# espurna-h.net
KiCad netlist of a schematic drawn in EAGLE
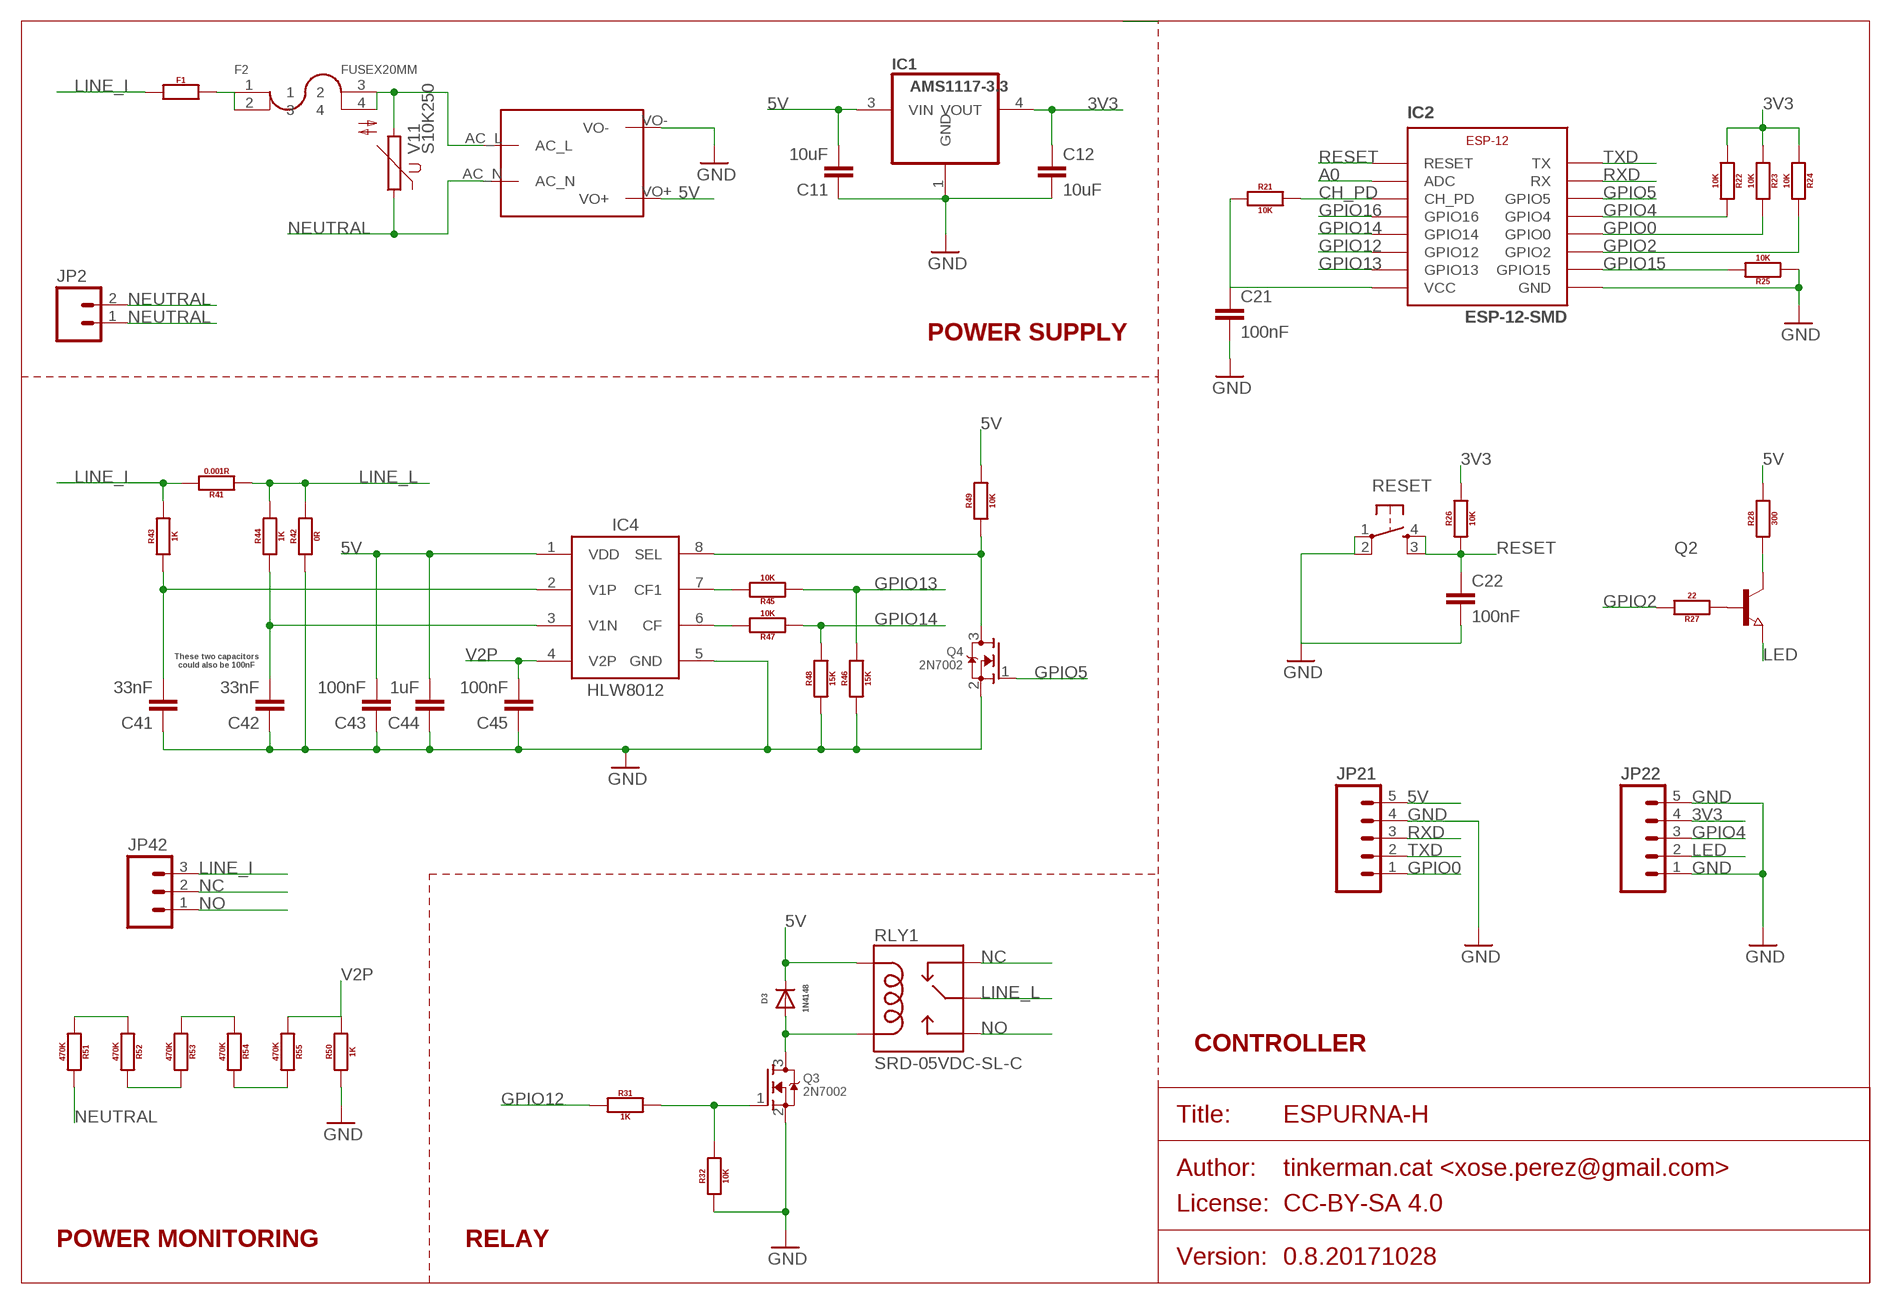
[diagram p0: schematic, sheet 1]

(export (version "E")
  (design (tool "Eeschema 10.0.6"))
  (components
    (comp (ref "C11")
      (value "10uF")
      (footprint "eagle-import:0805")
      (libsource (lib "eagle-import") (part "C-EU0805"))
    )
    (comp (ref "C12")
      (value "10uF")
      (footprint "eagle-import:0805")
      (libsource (lib "eagle-import") (part "C-EU0805"))
    )
    (comp (ref "C21")
      (value "100nF")
      (footprint "eagle-import:0805")
      (libsource (lib "eagle-import") (part "C-EU0805"))
    )
    (comp (ref "C22")
      (value "100nF")
      (footprint "eagle-import:0805")
      (libsource (lib "eagle-import") (part "C-EU0805"))
    )
    (comp (ref "C41")
      (value "33nF")
      (footprint "eagle-import:0805")
      (libsource (lib "eagle-import") (part "C-EU0805"))
    )
    (comp (ref "C42")
      (value "33nF")
      (footprint "eagle-import:0805")
      (libsource (lib "eagle-import") (part "C-EU0805"))
    )
    (comp (ref "C43")
      (value "100nF")
      (footprint "eagle-import:0805")
      (libsource (lib "eagle-import") (part "C-EU0805"))
    )
    (comp (ref "C44")
      (value "1uF")
      (footprint "eagle-import:0805")
      (libsource (lib "eagle-import") (part "C-EU0805"))
    )
    (comp (ref "C45")
      (value "100nF")
      (footprint "eagle-import:0805")
      (libsource (lib "eagle-import") (part "C-EU0805"))
    )
    (comp (ref "D3")
      (value "1N4148")
      (footprint "eagle-import:SOD80")
      (libsource (lib "eagle-import") (part "DIODE"))
    )
    (comp (ref "F1")
      (value "THERMALFUSE0.4")
      (footprint "eagle-import:AXIAL-0.4")
      (libsource (lib "eagle-import") (part "THERMALFUSE0.4"))
    )
    (comp (ref "F2")
      (value "FUSEX20MM")
      (footprint "eagle-import:FUSE_5MM")
      (libsource (lib "eagle-import") (part "FUSEX20MM"))
    )
    (comp (ref "IC1")
      (value "AMS1117-3.3")
      (footprint "eagle-import:SOT223")
      (libsource (lib "eagle-import") (part "REG1117SOT223-2"))
    )
    (comp (ref "IC2")
      (value "ESP-12-SMD")
      (footprint "eagle-import:ESP-12-SMD")
      (libsource (lib "eagle-import") (part "ESP-12-SMD"))
    )
    (comp (ref "IC4")
      (value "HLW8012")
      (footprint "eagle-import:SOP8")
      (libsource (lib "eagle-import") (part "HLW8012"))
    )
    (comp (ref "JP2")
      (value "M02200MIL")
      (footprint "eagle-import:SCREWTERMINAL-200MIL-2")
      (libsource (lib "eagle-import") (part "M02200MIL"))
    )
    (comp (ref "JP21")
      (value "M05PTH")
      (footprint "eagle-import:1X05")
      (libsource (lib "eagle-import") (part "M05PTH"))
    )
    (comp (ref "JP22")
      (value "M05PTH")
      (footprint "eagle-import:1X05")
      (libsource (lib "eagle-import") (part "M05PTH"))
    )
    (comp (ref "JP42")
      (value "M03200MIL")
      (footprint "eagle-import:SCREWTERMINAL-200MIL-3")
      (libsource (lib "eagle-import") (part "M03200MIL"))
    )
    (comp (ref "Q2")
      (value "NPN-TRANSISTOR_SOT23")
      (footprint "eagle-import:SOT23")
      (libsource (lib "eagle-import") (part "NPN-TRANSISTOR_SOT23"))
    )
    (comp (ref "Q3")
      (value "2N7002")
      (footprint "eagle-import:SOT23")
      (libsource (lib "eagle-import") (part "MOSFET-NREFLOW"))
    )
    (comp (ref "Q4")
      (value "2N7002")
      (footprint "eagle-import:SOT23")
      (libsource (lib "eagle-import") (part "MOSFET-NREFLOW"))
    )
    (comp (ref "R21")
      (value "10K")
      (footprint "eagle-import:0805")
      (libsource (lib "eagle-import") (part "RESISTOR0805"))
    )
    (comp (ref "R22")
      (value "10K")
      (footprint "eagle-import:0805")
      (libsource (lib "eagle-import") (part "RESISTOR0805"))
    )
    (comp (ref "R23")
      (value "10K")
      (footprint "eagle-import:0805")
      (libsource (lib "eagle-import") (part "RESISTOR0805"))
    )
    (comp (ref "R24")
      (value "10K")
      (footprint "eagle-import:0805")
      (libsource (lib "eagle-import") (part "RESISTOR0805"))
    )
    (comp (ref "R25")
      (value "10K")
      (footprint "eagle-import:0805")
      (libsource (lib "eagle-import") (part "RESISTOR0805"))
    )
    (comp (ref "R26")
      (value "10K")
      (footprint "eagle-import:0805")
      (libsource (lib "eagle-import") (part "RESISTOR0805"))
    )
    (comp (ref "R27")
      (value "22")
      (footprint "eagle-import:0805")
      (libsource (lib "eagle-import") (part "RESISTOR0805"))
    )
    (comp (ref "R28")
      (value "300")
      (footprint "eagle-import:0805")
      (libsource (lib "eagle-import") (part "RESISTOR0805"))
    )
    (comp (ref "R31")
      (value "1K")
      (footprint "eagle-import:0805")
      (libsource (lib "eagle-import") (part "RESISTOR0805"))
    )
    (comp (ref "R32")
      (value "10K")
      (footprint "eagle-import:0805")
      (libsource (lib "eagle-import") (part "RESISTOR0805"))
    )
    (comp (ref "R41")
      (value "0.001R")
      (footprint "eagle-import:2512")
      (libsource (lib "eagle-import") (part "RESISTOR2512"))
    )
    (comp (ref "R42")
      (value "0R")
      (footprint "eagle-import:1206")
      (libsource (lib "eagle-import") (part "RESISTOR1206"))
    )
    (comp (ref "R43")
      (value "1K")
      (footprint "eagle-import:0805")
      (libsource (lib "eagle-import") (part "RESISTOR0805"))
    )
    (comp (ref "R44")
      (value "1K")
      (footprint "eagle-import:0805")
      (libsource (lib "eagle-import") (part "RESISTOR0805"))
    )
    (comp (ref "R45")
      (value "10K")
      (footprint "eagle-import:0805")
      (libsource (lib "eagle-import") (part "RESISTOR0805"))
    )
    (comp (ref "R46")
      (value "15K")
      (footprint "eagle-import:0805")
      (libsource (lib "eagle-import") (part "RESISTOR0805"))
    )
    (comp (ref "R47")
      (value "10K")
      (footprint "eagle-import:0805")
      (libsource (lib "eagle-import") (part "RESISTOR0805"))
    )
    (comp (ref "R48")
      (value "15K")
      (footprint "eagle-import:0805")
      (libsource (lib "eagle-import") (part "RESISTOR0805"))
    )
    (comp (ref "R49")
      (value "10K")
      (footprint "eagle-import:0805")
      (libsource (lib "eagle-import") (part "RESISTOR0805"))
    )
    (comp (ref "R50")
      (value "1K")
      (footprint "eagle-import:0805")
      (libsource (lib "eagle-import") (part "RESISTOR0805"))
    )
    (comp (ref "R51")
      (value "470K")
      (footprint "eagle-import:0805")
      (libsource (lib "eagle-import") (part "RESISTOR0805"))
    )
    (comp (ref "R52")
      (value "470K")
      (footprint "eagle-import:0805")
      (libsource (lib "eagle-import") (part "RESISTOR0805"))
    )
    (comp (ref "R53")
      (value "470K")
      (footprint "eagle-import:0805")
      (libsource (lib "eagle-import") (part "RESISTOR0805"))
    )
    (comp (ref "R54")
      (value "470K")
      (footprint "eagle-import:0805")
      (libsource (lib "eagle-import") (part "RESISTOR0805"))
    )
    (comp (ref "R55")
      (value "470K")
      (footprint "eagle-import:0805")
      (libsource (lib "eagle-import") (part "RESISTOR0805"))
    )
    (comp (ref "RESET")
      (value "TACTILE_BUTTON_SMD")
      (footprint "eagle-import:TACTILE-BUTTON-SMD")
      (libsource (lib "eagle-import") (part "TACTILE_BUTTON_SMD"))
    )
    (comp (ref "RLY1")
      (value "SRD-05VDC-SL-C")
      (footprint "eagle-import:SRD-5VDC-SL-C")
      (libsource (lib "eagle-import") (part "RELAYSONGLE"))
    )
    (comp (ref "U$1")
      (value "MAINS_CONVERTERS")
      (footprint "eagle-import:HLK-PM01")
      (libsource (lib "eagle-import") (part "MAINS_CONVERTERS"))
    )
    (comp (ref "V11")
      (value "S10K250")
      (footprint "eagle-import:S10K250")
      (libsource (lib "eagle-import") (part "S10K250"))
    )
  )
  (nets
    (net (code "1") (name "/3V3") (class "Default")
      (node (ref "C12") (pin "1") (pinfunction "1_1") (pintype "passive"))
      (node (ref "C21") (pin "1") (pinfunction "1_1") (pintype "passive"))
      (node (ref "IC1") (pin "4") (pinfunction "VOUT_4") (pintype "output"))
      (node (ref "IC2") (pin "VCC") (pinfunction "VCC_VCC") (pintype "bidirectional"))
      (node (ref "JP22") (pin "4") (pinfunction "4_4") (pintype "passive"))
      (node (ref "R21") (pin "1") (pinfunction "1_1") (pintype "passive"))
      (node (ref "R22") (pin "1") (pinfunction "1_1") (pintype "passive"))
      (node (ref "R23") (pin "1") (pinfunction "1_1") (pintype "passive"))
      (node (ref "R24") (pin "1") (pinfunction "1_1") (pintype "passive"))
      (node (ref "R26") (pin "2") (pinfunction "2_2") (pintype "passive"))
    )
    (net (code "2") (name "/5V") (class "Default")
      (node (ref "C11") (pin "2") (pinfunction "2_2") (pintype "passive"))
      (node (ref "C43") (pin "2") (pinfunction "2_2") (pintype "passive"))
      (node (ref "C44") (pin "2") (pinfunction "2_2") (pintype "passive"))
      (node (ref "D3") (pin "2") (pinfunction "C_2") (pintype "passive"))
      (node (ref "IC1") (pin "3") (pinfunction "VIN_3") (pintype "input"))
      (node (ref "IC4") (pin "1") (pinfunction "VDD_1") (pintype "power_in"))
      (node (ref "JP21") (pin "5") (pinfunction "5_5") (pintype "passive"))
      (node (ref "R28") (pin "2") (pinfunction "2_2") (pintype "passive"))
      (node (ref "R49") (pin "2") (pinfunction "2_2") (pintype "passive"))
      (node (ref "RLY1") (pin "COIL1") (pinfunction "COIL1_COIL1") (pintype "bidirectional"))
      (node (ref "U$1") (pin "VO+") (pinfunction "VO+_VO+") (pintype "output"))
    )
    (net (code "3") (name "/A0") (class "Default")
      (node (ref "IC2") (pin "ADC") (pinfunction "ADC_ADC") (pintype "bidirectional"))
    )
    (net (code "4") (name "/CH_PD") (class "Default")
      (node (ref "IC2") (pin "CH_PD") (pinfunction "CH_PD_CH_PD") (pintype "bidirectional"))
      (node (ref "R21") (pin "2") (pinfunction "2_2") (pintype "passive"))
    )
    (net (code "5") (name "/GPIO0") (class "Default")
      (node (ref "IC2") (pin "GPIO0") (pinfunction "GPIO0_GPIO0") (pintype "bidirectional"))
      (node (ref "JP21") (pin "1") (pinfunction "1_1") (pintype "passive"))
      (node (ref "R23") (pin "2") (pinfunction "2_2") (pintype "passive"))
    )
    (net (code "6") (name "/GPIO2") (class "Default")
      (node (ref "IC2") (pin "GPIO2") (pinfunction "GPIO2_GPIO2") (pintype "bidirectional"))
      (node (ref "R24") (pin "2") (pinfunction "2_2") (pintype "passive"))
      (node (ref "R27") (pin "2") (pinfunction "2_2") (pintype "passive"))
    )
    (net (code "7") (name "/GPIO4") (class "Default")
      (node (ref "IC2") (pin "GPIO4") (pinfunction "GPIO4_GPIO4") (pintype "bidirectional"))
      (node (ref "JP22") (pin "3") (pinfunction "3_3") (pintype "passive"))
      (node (ref "R22") (pin "2") (pinfunction "2_2") (pintype "passive"))
    )
    (net (code "8") (name "/GPIO5") (class "Default")
      (node (ref "IC2") (pin "GPIO5") (pinfunction "GPIO5_GPIO5") (pintype "bidirectional"))
      (node (ref "Q4") (pin "1") (pinfunction "G_1") (pintype "bidirectional"))
    )
    (net (code "9") (name "/GPIO12") (class "Default")
      (node (ref "IC2") (pin "GPIO12") (pinfunction "GPIO12_GPIO12") (pintype "bidirectional"))
      (node (ref "R31") (pin "1") (pinfunction "1_1") (pintype "passive"))
    )
    (net (code "10") (name "/GPIO13") (class "Default")
      (node (ref "IC2") (pin "GPIO13") (pinfunction "GPIO13_GPIO13") (pintype "bidirectional"))
      (node (ref "R45") (pin "1") (pinfunction "1_1") (pintype "passive"))
      (node (ref "R46") (pin "2") (pinfunction "2_2") (pintype "passive"))
    )
    (net (code "11") (name "/GPIO14") (class "Default")
      (node (ref "IC2") (pin "GPIO14") (pinfunction "GPIO14_GPIO14") (pintype "bidirectional"))
      (node (ref "R47") (pin "1") (pinfunction "1_1") (pintype "passive"))
      (node (ref "R48") (pin "2") (pinfunction "2_2") (pintype "passive"))
    )
    (net (code "12") (name "/GPIO15") (class "Default")
      (node (ref "IC2") (pin "GPIO15") (pinfunction "GPIO15_GPIO15") (pintype "bidirectional"))
      (node (ref "R25") (pin "2") (pinfunction "2_2") (pintype "passive"))
    )
    (net (code "13") (name "/GPIO16") (class "Default")
      (node (ref "IC2") (pin "GPIO16") (pinfunction "GPIO16_GPIO16") (pintype "bidirectional"))
    )
    (net (code "14") (name "/LED") (class "Default")
      (node (ref "JP22") (pin "2") (pinfunction "2_2") (pintype "passive"))
      (node (ref "Q2") (pin "2") (pinfunction "E_2") (pintype "passive"))
    )
    (net (code "15") (name "/LINE_I") (class "Default")
      (node (ref "F1") (pin "P$1") (pinfunction "1_P$1") (pintype "passive"))
      (node (ref "JP42") (pin "3") (pinfunction "3_3") (pintype "passive"))
      (node (ref "R41") (pin "2") (pinfunction "2_2") (pintype "passive"))
      (node (ref "R43") (pin "2") (pinfunction "2_2") (pintype "passive"))
    )
    (net (code "16") (name "/LINE_L") (class "Default")
      (node (ref "R41") (pin "1") (pinfunction "1_1") (pintype "passive"))
      (node (ref "R42") (pin "2") (pinfunction "2_2") (pintype "passive"))
      (node (ref "R44") (pin "2") (pinfunction "2_2") (pintype "passive"))
      (node (ref "RLY1") (pin "COMMON") (pinfunction "MAIN_COMMON") (pintype "bidirectional"))
    )
    (net (code "17") (name "/NC") (class "Default")
      (node (ref "JP42") (pin "2") (pinfunction "2_2") (pintype "passive"))
      (node (ref "RLY1") (pin "CLOSED") (pinfunction "NC_CLOSED") (pintype "bidirectional"))
    )
    (net (code "18") (name "/NEUTRAL") (class "Default")
      (node (ref "JP2") (pin "1") (pinfunction "1_1") (pintype "passive"))
      (node (ref "JP2") (pin "2") (pinfunction "2_2") (pintype "passive"))
      (node (ref "R51") (pin "2") (pinfunction "2_2") (pintype "passive"))
      (node (ref "U$1") (pin "AC_N") (pinfunction "AC_N_AC_N") (pintype "input"))
      (node (ref "V11") (pin "1") (pinfunction "1_1") (pintype "passive"))
    )
    (net (code "19") (name "/NO") (class "Default")
      (node (ref "JP42") (pin "1") (pinfunction "1_1") (pintype "passive"))
      (node (ref "RLY1") (pin "OPEN") (pinfunction "NO_OPEN") (pintype "bidirectional"))
    )
    (net (code "20") (name "/RESET") (class "Default")
      (node (ref "C22") (pin "1") (pinfunction "1_1") (pintype "passive"))
      (node (ref "IC2") (pin "RESET") (pinfunction "RESET_RESET") (pintype "bidirectional"))
      (node (ref "R26") (pin "1") (pinfunction "1_1") (pintype "passive"))
      (node (ref "RESET") (pin "3") (pinfunction "SWB2_3") (pintype "passive"))
      (node (ref "RESET") (pin "4") (pinfunction "SWA2_4") (pintype "passive"))
    )
    (net (code "21") (name "/RXD") (class "Default")
      (node (ref "IC2") (pin "RX") (pinfunction "RX_RX") (pintype "bidirectional"))
      (node (ref "JP21") (pin "3") (pinfunction "3_3") (pintype "passive"))
    )
    (net (code "22") (name "/TXD") (class "Default")
      (node (ref "IC2") (pin "TX") (pinfunction "TX_TX") (pintype "bidirectional"))
      (node (ref "JP21") (pin "2") (pinfunction "2_2") (pintype "passive"))
    )
    (net (code "23") (name "/V2P") (class "Default")
      (node (ref "C45") (pin "2") (pinfunction "2_2") (pintype "passive"))
      (node (ref "IC4") (pin "4") (pinfunction "V2P_4") (pintype "input"))
      (node (ref "R50") (pin "2") (pinfunction "2_2") (pintype "passive"))
      (node (ref "R55") (pin "1") (pinfunction "1_1") (pintype "passive"))
    )
    (net (code "24") (name "GND") (class "Default")
      (node (ref "C11") (pin "1") (pinfunction "1_1") (pintype "passive"))
      (node (ref "C12") (pin "2") (pinfunction "2_2") (pintype "passive"))
      (node (ref "C21") (pin "2") (pinfunction "2_2") (pintype "passive"))
      (node (ref "C22") (pin "2") (pinfunction "2_2") (pintype "passive"))
      (node (ref "C41") (pin "1") (pinfunction "1_1") (pintype "passive"))
      (node (ref "C42") (pin "1") (pinfunction "1_1") (pintype "passive"))
      (node (ref "C43") (pin "1") (pinfunction "1_1") (pintype "passive"))
      (node (ref "C44") (pin "1") (pinfunction "1_1") (pintype "passive"))
      (node (ref "C45") (pin "1") (pinfunction "1_1") (pintype "passive"))
      (node (ref "IC1") (pin "1") (pinfunction "GND_1") (pintype "power_in"))
      (node (ref "IC2") (pin "GND") (pinfunction "GND_GND") (pintype "bidirectional"))
      (node (ref "IC4") (pin "5") (pinfunction "GND_5") (pintype "power_in"))
      (node (ref "JP21") (pin "4") (pinfunction "4_4") (pintype "passive"))
      (node (ref "JP22") (pin "1") (pinfunction "1_1") (pintype "passive"))
      (node (ref "JP22") (pin "5") (pinfunction "5_5") (pintype "passive"))
      (node (ref "Q3") (pin "2") (pinfunction "S_2") (pintype "bidirectional"))
      (node (ref "Q4") (pin "2") (pinfunction "S_2") (pintype "bidirectional"))
      (node (ref "R25") (pin "1") (pinfunction "1_1") (pintype "passive"))
      (node (ref "R32") (pin "1") (pinfunction "1_1") (pintype "passive"))
      (node (ref "R42") (pin "1") (pinfunction "1_1") (pintype "passive"))
      (node (ref "R46") (pin "1") (pinfunction "1_1") (pintype "passive"))
      (node (ref "R48") (pin "1") (pinfunction "1_1") (pintype "passive"))
      (node (ref "R50") (pin "1") (pinfunction "1_1") (pintype "passive"))
      (node (ref "RESET") (pin "1") (pinfunction "SWA1_1") (pintype "passive"))
      (node (ref "RESET") (pin "2") (pinfunction "SWB1_2") (pintype "passive"))
      (node (ref "U$1") (pin "VO-") (pinfunction "VO-_VO-") (pintype "output"))
    )
    (net (code "25") (name "Net-(D3-A)") (class "Default")
      (node (ref "D3") (pin "1") (pinfunction "A_1") (pintype "passive"))
      (node (ref "Q3") (pin "3") (pinfunction "D_3") (pintype "bidirectional"))
      (node (ref "RLY1") (pin "COIL2") (pinfunction "COIL2_COIL2") (pintype "bidirectional"))
    )
    (net (code "26") (name "Net-(F1-2)") (class "Default")
      (node (ref "F1") (pin "P$2") (pinfunction "2_P$2") (pintype "passive"))
      (node (ref "F2") (pin "1") (pinfunction "1_1") (pintype "bidirectional"))
      (node (ref "F2") (pin "2") (pinfunction "3_2") (pintype "bidirectional"))
    )
    (net (code "27") (name "Net-(F2-2)") (class "Default")
      (node (ref "F2") (pin "3") (pinfunction "2_3") (pintype "bidirectional"))
      (node (ref "F2") (pin "4") (pinfunction "4_4") (pintype "bidirectional"))
      (node (ref "U$1") (pin "AC_L") (pinfunction "AC_L_AC_L") (pintype "input"))
      (node (ref "V11") (pin "2") (pinfunction "2_2") (pintype "passive"))
    )
    (net (code "28") (name "Net-(IC4-CF)") (class "Default")
      (node (ref "IC4") (pin "6") (pinfunction "CF_6") (pintype "output"))
      (node (ref "R47") (pin "2") (pinfunction "2_2") (pintype "passive"))
    )
    (net (code "29") (name "Net-(IC4-CF1)") (class "Default")
      (node (ref "IC4") (pin "7") (pinfunction "CF1_7") (pintype "output"))
      (node (ref "R45") (pin "2") (pinfunction "2_2") (pintype "passive"))
    )
    (net (code "30") (name "Net-(IC4-SEL)") (class "Default")
      (node (ref "IC4") (pin "8") (pinfunction "SEL_8") (pintype "input"))
      (node (ref "Q4") (pin "3") (pinfunction "D_3") (pintype "bidirectional"))
      (node (ref "R49") (pin "1") (pinfunction "1_1") (pintype "passive"))
    )
    (net (code "31") (name "Net-(IC4-V1N)") (class "Default")
      (node (ref "C42") (pin "2") (pinfunction "2_2") (pintype "passive"))
      (node (ref "IC4") (pin "3") (pinfunction "V1N_3") (pintype "input"))
      (node (ref "R44") (pin "1") (pinfunction "1_1") (pintype "passive"))
    )
    (net (code "32") (name "Net-(IC4-V1P)") (class "Default")
      (node (ref "C41") (pin "2") (pinfunction "2_2") (pintype "passive"))
      (node (ref "IC4") (pin "2") (pinfunction "V1P_2") (pintype "input"))
      (node (ref "R43") (pin "1") (pinfunction "1_1") (pintype "passive"))
    )
    (net (code "33") (name "Net-(Q2-B)") (class "Default")
      (node (ref "Q2") (pin "1") (pinfunction "B_1") (pintype "passive"))
      (node (ref "R27") (pin "1") (pinfunction "1_1") (pintype "passive"))
    )
    (net (code "34") (name "Net-(Q2-C)") (class "Default")
      (node (ref "Q2") (pin "3") (pinfunction "C_3") (pintype "passive"))
      (node (ref "R28") (pin "1") (pinfunction "1_1") (pintype "passive"))
    )
    (net (code "35") (name "Net-(Q3-G)") (class "Default")
      (node (ref "Q3") (pin "1") (pinfunction "G_1") (pintype "bidirectional"))
      (node (ref "R31") (pin "2") (pinfunction "2_2") (pintype "passive"))
      (node (ref "R32") (pin "2") (pinfunction "2_2") (pintype "passive"))
    )
    (net (code "36") (name "Net-(R51-Pad1)") (class "Default")
      (node (ref "R51") (pin "1") (pinfunction "1_1") (pintype "passive"))
      (node (ref "R52") (pin "1") (pinfunction "1_1") (pintype "passive"))
    )
    (net (code "37") (name "Net-(R52-Pad2)") (class "Default")
      (node (ref "R52") (pin "2") (pinfunction "2_2") (pintype "passive"))
      (node (ref "R53") (pin "2") (pinfunction "2_2") (pintype "passive"))
    )
    (net (code "38") (name "Net-(R53-Pad1)") (class "Default")
      (node (ref "R53") (pin "1") (pinfunction "1_1") (pintype "passive"))
      (node (ref "R54") (pin "1") (pinfunction "1_1") (pintype "passive"))
    )
    (net (code "39") (name "Net-(R54-Pad2)") (class "Default")
      (node (ref "R54") (pin "2") (pinfunction "2_2") (pintype "passive"))
      (node (ref "R55") (pin "2") (pinfunction "2_2") (pintype "passive"))
    )
  )
)
